# ATF1504JTAG.net
KiCad netlist of a schematic drawn in EAGLE
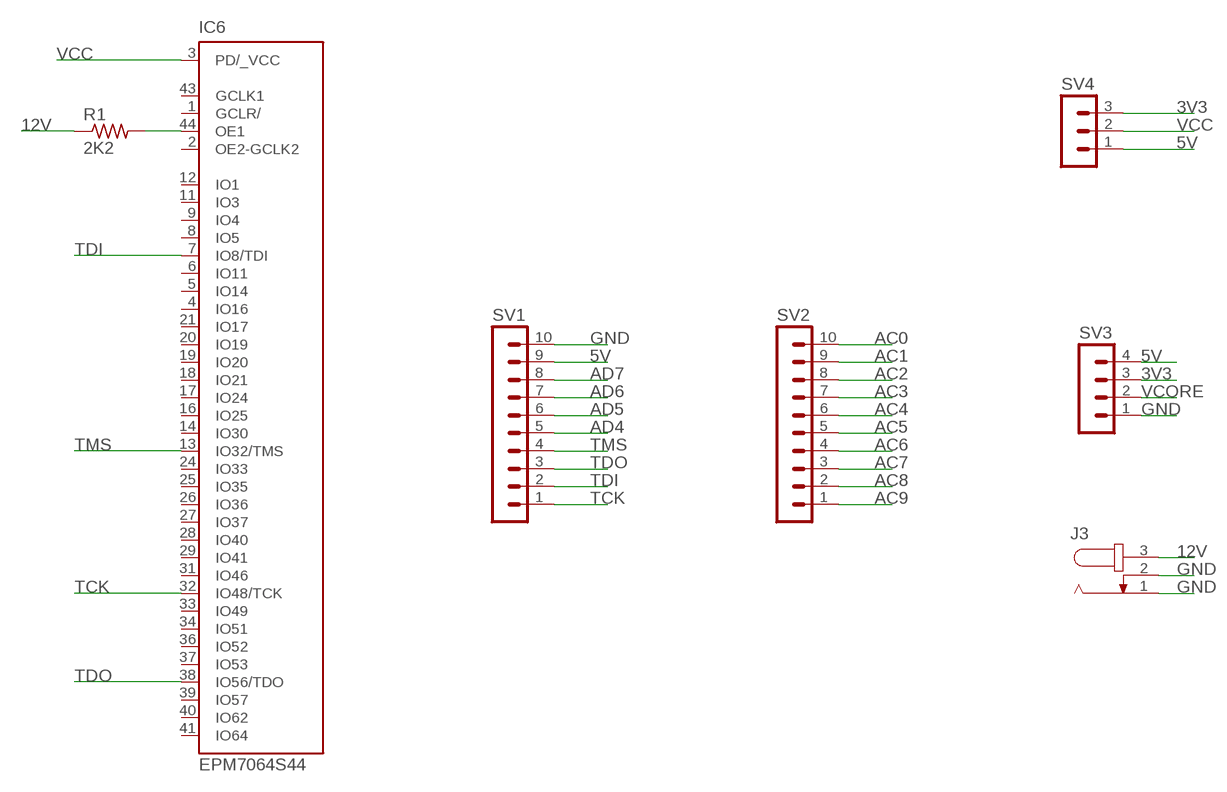
[diagram p0: schematic, sheet 1]

(export (version "E")
  (design (tool "Eeschema 10.0.6"))
  (components
    (comp (ref "IC6")
      (value "EPM7064S44")
      (footprint "eagle-import:PLCC-S44")
      (fields (field (name "MPN") "EPM7064SLC44-10N"))
      (libsource (lib "eagle-import") (part "EPM7064S44"))
    )
    (comp (ref "J3")
      (value "JACK-PLUG1")
      (footprint "eagle-import:SPC4078")
      (libsource (lib "eagle-import") (part "JACK-PLUG1"))
    )
    (comp (ref "R1")
      (value "2K2")
      (footprint "eagle-import:0207_10")
      (libsource (lib "eagle-import") (part "R-US_0207/10"))
    )
    (comp (ref "SV1")
      (value "MA10-1")
      (footprint "eagle-import:MA10-1")
      (libsource (lib "eagle-import") (part "MA10-1"))
    )
    (comp (ref "SV2")
      (value "MA10-1")
      (footprint "eagle-import:MA10-1")
      (libsource (lib "eagle-import") (part "MA10-1"))
    )
    (comp (ref "SV3")
      (value "MA04-1")
      (footprint "eagle-import:MA04-1")
      (libsource (lib "eagle-import") (part "MA04-1"))
    )
    (comp (ref "SV4")
      (value "MA03-1")
      (footprint "eagle-import:MA03-1")
      (libsource (lib "eagle-import") (part "MA03-1"))
    )
  )
  (nets
    (net (code "1") (name "/3V3") (class "Default")
      (node (ref "SV3") (pin "3") (pinfunction "3_3") (pintype "passive"))
      (node (ref "SV4") (pin "3") (pinfunction "3_3") (pintype "passive"))
    )
    (net (code "2") (name "/5V") (class "Default")
      (node (ref "SV1") (pin "9") (pinfunction "9_9") (pintype "passive"))
      (node (ref "SV3") (pin "4") (pinfunction "4_4") (pintype "passive"))
      (node (ref "SV4") (pin "1") (pinfunction "1_1") (pintype "passive"))
    )
    (net (code "3") (name "/12V") (class "Default")
      (node (ref "J3") (pin "3") (pinfunction "3_3") (pintype "passive"))
      (node (ref "R1") (pin "1") (pinfunction "1_1") (pintype "passive"))
    )
    (net (code "4") (name "/AC0") (class "Default")
      (node (ref "SV2") (pin "10") (pinfunction "10_10") (pintype "passive"))
    )
    (net (code "5") (name "/AC1") (class "Default")
      (node (ref "SV2") (pin "9") (pinfunction "9_9") (pintype "passive"))
    )
    (net (code "6") (name "/AC2") (class "Default")
      (node (ref "SV2") (pin "8") (pinfunction "8_8") (pintype "passive"))
    )
    (net (code "7") (name "/AC3") (class "Default")
      (node (ref "SV2") (pin "7") (pinfunction "7_7") (pintype "passive"))
    )
    (net (code "8") (name "/AC4") (class "Default")
      (node (ref "SV2") (pin "6") (pinfunction "6_6") (pintype "passive"))
    )
    (net (code "9") (name "/AC5") (class "Default")
      (node (ref "SV2") (pin "5") (pinfunction "5_5") (pintype "passive"))
    )
    (net (code "10") (name "/AC6") (class "Default")
      (node (ref "SV2") (pin "4") (pinfunction "4_4") (pintype "passive"))
    )
    (net (code "11") (name "/AC7") (class "Default")
      (node (ref "SV2") (pin "3") (pinfunction "3_3") (pintype "passive"))
    )
    (net (code "12") (name "/AC8") (class "Default")
      (node (ref "SV2") (pin "2") (pinfunction "2_2") (pintype "passive"))
    )
    (net (code "13") (name "/AC9") (class "Default")
      (node (ref "SV2") (pin "1") (pinfunction "1_1") (pintype "passive"))
    )
    (net (code "14") (name "/AD4") (class "Default")
      (node (ref "SV1") (pin "5") (pinfunction "5_5") (pintype "passive"))
    )
    (net (code "15") (name "/AD5") (class "Default")
      (node (ref "SV1") (pin "6") (pinfunction "6_6") (pintype "passive"))
    )
    (net (code "16") (name "/AD6") (class "Default")
      (node (ref "SV1") (pin "7") (pinfunction "7_7") (pintype "passive"))
    )
    (net (code "17") (name "/AD7") (class "Default")
      (node (ref "SV1") (pin "8") (pinfunction "8_8") (pintype "passive"))
    )
    (net (code "18") (name "/GND") (class "Default")
      (node (ref "J3") (pin "1") (pinfunction "1_1") (pintype "passive"))
      (node (ref "J3") (pin "2") (pinfunction "2_2") (pintype "passive"))
      (node (ref "SV1") (pin "10") (pinfunction "10_10") (pintype "passive"))
      (node (ref "SV3") (pin "1") (pinfunction "1_1") (pintype "passive"))
    )
    (net (code "19") (name "/TCK") (class "Default")
      (node (ref "IC6") (pin "32") (pinfunction "IO48/TCK_32") (pintype "bidirectional"))
      (node (ref "SV1") (pin "1") (pinfunction "1_1") (pintype "passive"))
    )
    (net (code "20") (name "/TDI") (class "Default")
      (node (ref "IC6") (pin "7") (pinfunction "IO8/TDI_7") (pintype "bidirectional"))
      (node (ref "SV1") (pin "2") (pinfunction "2_2") (pintype "passive"))
    )
    (net (code "21") (name "/TDO") (class "Default")
      (node (ref "IC6") (pin "38") (pinfunction "IO56/TDO_38") (pintype "bidirectional"))
      (node (ref "SV1") (pin "3") (pinfunction "3_3") (pintype "passive"))
    )
    (net (code "22") (name "/TMS") (class "Default")
      (node (ref "IC6") (pin "13") (pinfunction "IO32/TMS_13") (pintype "bidirectional"))
      (node (ref "SV1") (pin "4") (pinfunction "4_4") (pintype "passive"))
    )
    (net (code "23") (name "/VCC") (class "Default")
      (node (ref "IC6") (pin "3") (pinfunction "PD/_VCC_3") (pintype "passive"))
      (node (ref "SV4") (pin "2") (pinfunction "2_2") (pintype "passive"))
    )
    (net (code "24") (name "/VCORE") (class "Default")
      (node (ref "SV3") (pin "2") (pinfunction "2_2") (pintype "passive"))
    )
    (net (code "25") (name "Net-(IC6A-OE1)") (class "Default")
      (node (ref "IC6") (pin "44") (pinfunction "OE1_44") (pintype "input"))
      (node (ref "R1") (pin "2") (pinfunction "2_2") (pintype "passive"))
    )
    (net (code "26") (name "unconnected-(IC6A-GCLK1-Pad43)") (class "Default")
      (node (ref "IC6") (pin "43") (pinfunction "GCLK1_43") (pintype "input"))
    )
    (net (code "27") (name "unconnected-(IC6A-GCLR{slash}-Pad1)") (class "Default")
      (node (ref "IC6") (pin "1") (pinfunction "GCLR/_1") (pintype "input"))
    )
    (net (code "28") (name "unconnected-(IC6A-IO1-Pad12)") (class "Default")
      (node (ref "IC6") (pin "12") (pinfunction "IO1_12") (pintype "bidirectional"))
    )
    (net (code "29") (name "unconnected-(IC6A-IO3-Pad11)") (class "Default")
      (node (ref "IC6") (pin "11") (pinfunction "IO3_11") (pintype "bidirectional"))
    )
    (net (code "30") (name "unconnected-(IC6A-IO4-Pad9)") (class "Default")
      (node (ref "IC6") (pin "9") (pinfunction "IO4_9") (pintype "bidirectional"))
    )
    (net (code "31") (name "unconnected-(IC6A-IO5-Pad8)") (class "Default")
      (node (ref "IC6") (pin "8") (pinfunction "IO5_8") (pintype "bidirectional"))
    )
    (net (code "32") (name "unconnected-(IC6A-IO11-Pad6)") (class "Default")
      (node (ref "IC6") (pin "6") (pinfunction "IO11_6") (pintype "bidirectional"))
    )
    (net (code "33") (name "unconnected-(IC6A-IO14-Pad5)") (class "Default")
      (node (ref "IC6") (pin "5") (pinfunction "IO14_5") (pintype "bidirectional"))
    )
    (net (code "34") (name "unconnected-(IC6A-IO16-Pad4)") (class "Default")
      (node (ref "IC6") (pin "4") (pinfunction "IO16_4") (pintype "bidirectional"))
    )
    (net (code "35") (name "unconnected-(IC6A-IO17-Pad21)") (class "Default")
      (node (ref "IC6") (pin "21") (pinfunction "IO17_21") (pintype "bidirectional"))
    )
    (net (code "36") (name "unconnected-(IC6A-IO19-Pad20)") (class "Default")
      (node (ref "IC6") (pin "20") (pinfunction "IO19_20") (pintype "bidirectional"))
    )
    (net (code "37") (name "unconnected-(IC6A-IO20-Pad19)") (class "Default")
      (node (ref "IC6") (pin "19") (pinfunction "IO20_19") (pintype "bidirectional"))
    )
    (net (code "38") (name "unconnected-(IC6A-IO21-Pad18)") (class "Default")
      (node (ref "IC6") (pin "18") (pinfunction "IO21_18") (pintype "bidirectional"))
    )
    (net (code "39") (name "unconnected-(IC6A-IO24-Pad17)") (class "Default")
      (node (ref "IC6") (pin "17") (pinfunction "IO24_17") (pintype "bidirectional"))
    )
    (net (code "40") (name "unconnected-(IC6A-IO25-Pad16)") (class "Default")
      (node (ref "IC6") (pin "16") (pinfunction "IO25_16") (pintype "bidirectional"))
    )
    (net (code "41") (name "unconnected-(IC6A-IO30-Pad14)") (class "Default")
      (node (ref "IC6") (pin "14") (pinfunction "IO30_14") (pintype "bidirectional"))
    )
    (net (code "42") (name "unconnected-(IC6A-IO33-Pad24)") (class "Default")
      (node (ref "IC6") (pin "24") (pinfunction "IO33_24") (pintype "bidirectional"))
    )
    (net (code "43") (name "unconnected-(IC6A-IO35-Pad25)") (class "Default")
      (node (ref "IC6") (pin "25") (pinfunction "IO35_25") (pintype "bidirectional"))
    )
    (net (code "44") (name "unconnected-(IC6A-IO36-Pad26)") (class "Default")
      (node (ref "IC6") (pin "26") (pinfunction "IO36_26") (pintype "bidirectional"))
    )
    (net (code "45") (name "unconnected-(IC6A-IO37-Pad27)") (class "Default")
      (node (ref "IC6") (pin "27") (pinfunction "IO37_27") (pintype "bidirectional"))
    )
    (net (code "46") (name "unconnected-(IC6A-IO40-Pad28)") (class "Default")
      (node (ref "IC6") (pin "28") (pinfunction "IO40_28") (pintype "bidirectional"))
    )
    (net (code "47") (name "unconnected-(IC6A-IO41-Pad29)") (class "Default")
      (node (ref "IC6") (pin "29") (pinfunction "IO41_29") (pintype "bidirectional"))
    )
    (net (code "48") (name "unconnected-(IC6A-IO46-Pad31)") (class "Default")
      (node (ref "IC6") (pin "31") (pinfunction "IO46_31") (pintype "bidirectional"))
    )
    (net (code "49") (name "unconnected-(IC6A-IO49-Pad33)") (class "Default")
      (node (ref "IC6") (pin "33") (pinfunction "IO49_33") (pintype "bidirectional"))
    )
    (net (code "50") (name "unconnected-(IC6A-IO51-Pad34)") (class "Default")
      (node (ref "IC6") (pin "34") (pinfunction "IO51_34") (pintype "bidirectional"))
    )
    (net (code "51") (name "unconnected-(IC6A-IO52-Pad36)") (class "Default")
      (node (ref "IC6") (pin "36") (pinfunction "IO52_36") (pintype "bidirectional"))
    )
    (net (code "52") (name "unconnected-(IC6A-IO53-Pad37)") (class "Default")
      (node (ref "IC6") (pin "37") (pinfunction "IO53_37") (pintype "bidirectional"))
    )
    (net (code "53") (name "unconnected-(IC6A-IO57-Pad39)") (class "Default")
      (node (ref "IC6") (pin "39") (pinfunction "IO57_39") (pintype "bidirectional"))
    )
    (net (code "54") (name "unconnected-(IC6A-IO62-Pad40)") (class "Default")
      (node (ref "IC6") (pin "40") (pinfunction "IO62_40") (pintype "bidirectional"))
    )
    (net (code "55") (name "unconnected-(IC6A-IO64-Pad41)") (class "Default")
      (node (ref "IC6") (pin "41") (pinfunction "IO64_41") (pintype "bidirectional"))
    )
    (net (code "56") (name "unconnected-(IC6A-OE2-GCLK2-Pad2)") (class "Default")
      (node (ref "IC6") (pin "2") (pinfunction "OE2-GCLK2_2") (pintype "input"))
    )
  )
)
